# Snowflake.net
KiCad netlist of a schematic drawn in Altium Designer
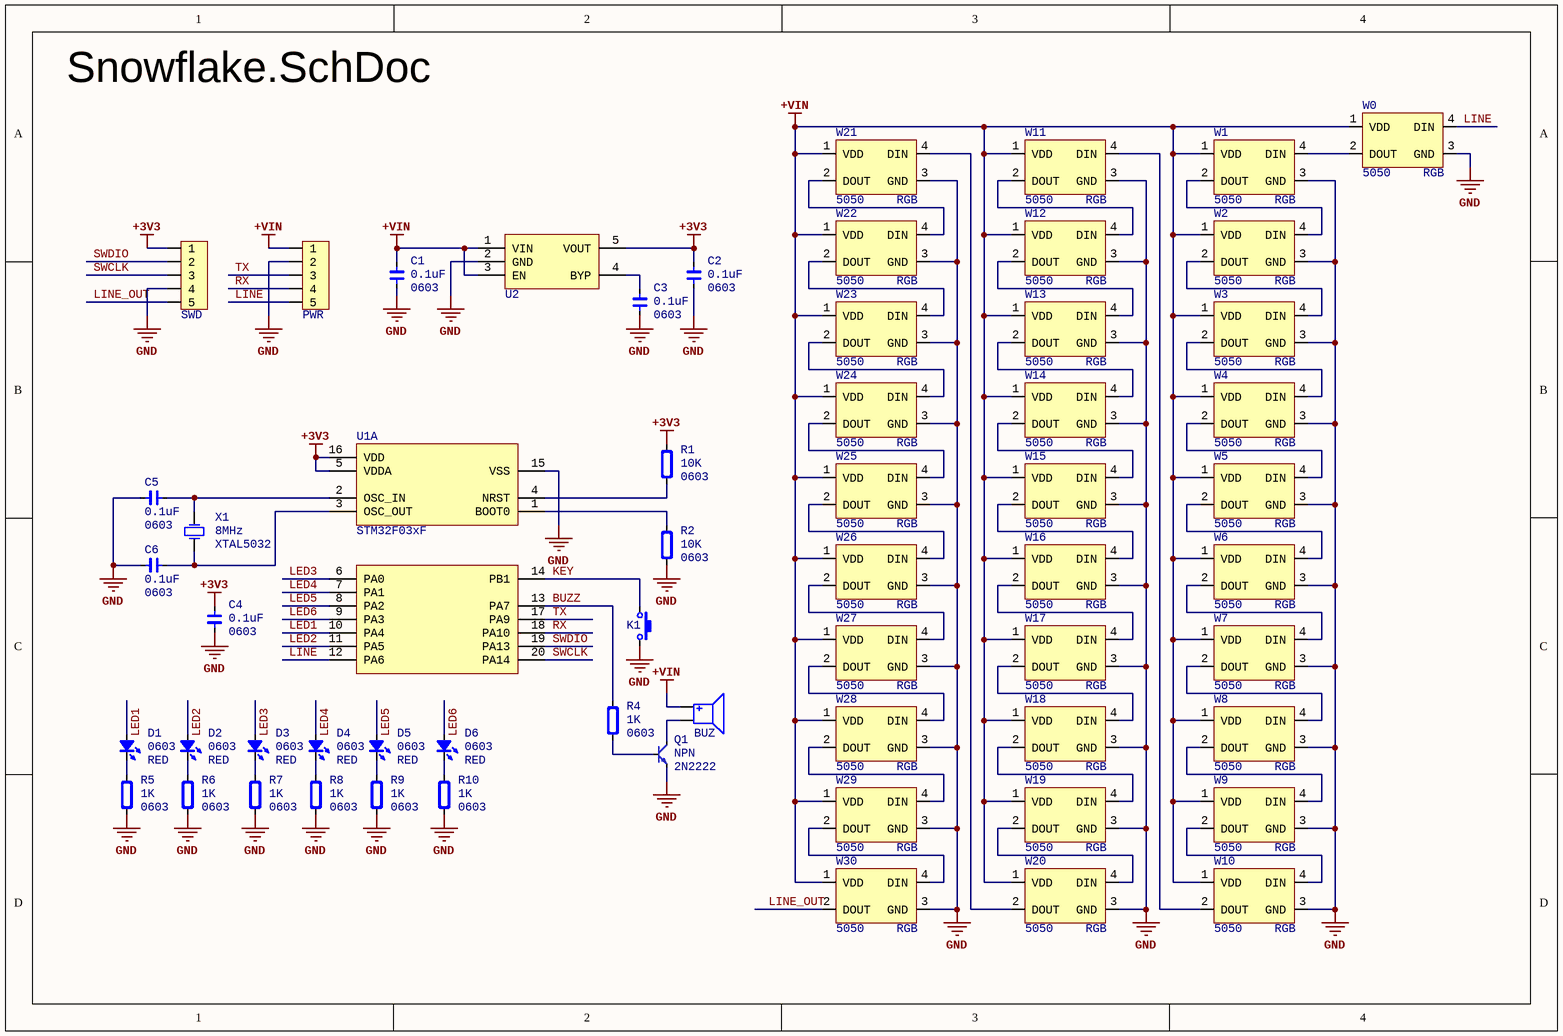
[diagram p0: Snowflake.SchDoc]

(export (version "E")
  (design (tool "Eeschema 10.0.6"))
  (components
    (comp (ref "BUZ")
      (value "Buzzer")
      (footprint "PCB_Module:Buzzer_5x5")
      (libsource (lib "SCH_Module") (part "Buzzer"))
    )
    (comp (ref "C1")
      (value "0.1uF")
      (footprint "PCB_PassiveCap:CAP_0603")
      (description "Capacitor")
      (fields (field (name "TYPE") "0603"))
      (libsource (lib "SCH_Passive") (part "Cap_0603"))
    )
    (comp (ref "C2")
      (value "0.1uF")
      (footprint "PCB_PassiveCap:CAP_0603")
      (description "Capacitor")
      (fields (field (name "TYPE") "0603"))
      (libsource (lib "SCH_Passive") (part "Cap_0603"))
    )
    (comp (ref "C3")
      (value "0.1uF")
      (footprint "PCB_PassiveCap:CAP_0603")
      (description "Capacitor")
      (fields (field (name "TYPE") "0603"))
      (libsource (lib "SCH_Passive") (part "Cap_0603"))
    )
    (comp (ref "C4")
      (value "0.1uF")
      (footprint "PCB_PassiveCap:CAP_0603")
      (description "Capacitor")
      (fields (field (name "TYPE") "0603"))
      (libsource (lib "SCH_Passive") (part "Cap_0603"))
    )
    (comp (ref "C5")
      (value "0.1uF")
      (footprint "PCB_PassiveCap:CAP_0603")
      (description "Capacitor")
      (fields (field (name "TYPE") "0603"))
      (libsource (lib "") (part "Cap_0603_1"))
    )
    (comp (ref "C6")
      (value "0.1uF")
      (footprint "PCB_PassiveCap:CAP_0603")
      (description "Capacitor")
      (fields (field (name "TYPE") "0603"))
      (libsource (lib "") (part "Cap_0603_1"))
    )
    (comp (ref "D1")
      (value "RED")
      (footprint "PCB_ActiveLED:LED_0603_RED")
      (description "LED")
      (fields (field (name "TYPE") "0603"))
      (libsource (lib "SCH_Active") (part "LED_0603"))
    )
    (comp (ref "D2")
      (value "RED")
      (footprint "PCB_ActiveLED:LED_0603_RED")
      (description "LED")
      (fields (field (name "TYPE") "0603"))
      (libsource (lib "SCH_Active") (part "LED_0603"))
    )
    (comp (ref "D3")
      (value "RED")
      (footprint "PCB_ActiveLED:LED_0603_RED")
      (description "LED")
      (fields (field (name "TYPE") "0603"))
      (libsource (lib "SCH_Active") (part "LED_0603"))
    )
    (comp (ref "D4")
      (value "RED")
      (footprint "PCB_ActiveLED:LED_0603_RED")
      (description "LED")
      (fields (field (name "TYPE") "0603"))
      (libsource (lib "SCH_Active") (part "LED_0603"))
    )
    (comp (ref "D5")
      (value "RED")
      (footprint "PCB_ActiveLED:LED_0603_RED")
      (description "LED")
      (fields (field (name "TYPE") "0603"))
      (libsource (lib "SCH_Active") (part "LED_0603"))
    )
    (comp (ref "D6")
      (value "RED")
      (footprint "PCB_ActiveLED:LED_0603_RED")
      (description "LED")
      (fields (field (name "TYPE") "0603"))
      (libsource (lib "SCH_Active") (part "LED_0603"))
    )
    (comp (ref "K1")
      (value "ButtonTACT")
      (footprint "PCB_Switch:ButtonTACT_3x4x2_180")
      (description "Button")
      (libsource (lib "SCH_Switch") (part "ButtonTACT_3x4x2_180"))
    )
    (comp (ref "PWR")
      (value "HDR1x5_2.54")
      (footprint "PCB_ConnectorHDR:HDR1X5_2.54_180")
      (description "Header")
      (libsource (lib "SCH_ConnectorHDR") (part "HDR1x5_2.54"))
    )
    (comp (ref "Q1")
      (value "NPN")
      (footprint "PCB_IntegratedCircuit:SOT23-3")
      (description "Transistor")
      (fields (field (name "TYPE") "2N2222"))
      (libsource (lib "SCH_Active") (part "BJT_NPN"))
    )
    (comp (ref "R1")
      (value "10K")
      (footprint "PCB_PassiveRes:RES_0603")
      (description "Resistor")
      (fields (field (name "TYPE") "0603"))
      (libsource (lib "SCH_Passive") (part "Res_0603"))
    )
    (comp (ref "R2")
      (value "10K")
      (footprint "PCB_PassiveRes:RES_0603")
      (description "Resistor")
      (fields (field (name "TYPE") "0603"))
      (libsource (lib "SCH_Passive") (part "Res_0603"))
    )
    (comp (ref "R4")
      (value "1K")
      (footprint "PCB_PassiveRes:RES_0603")
      (description "Resistor")
      (fields (field (name "TYPE") "0603"))
      (libsource (lib "SCH_Passive") (part "Res_0603"))
    )
    (comp (ref "R5")
      (value "1K")
      (footprint "PCB_PassiveRes:RES_0603")
      (description "Resistor")
      (fields (field (name "TYPE") "0603"))
      (libsource (lib "SCH_Passive") (part "Res_0603"))
    )
    (comp (ref "R6")
      (value "1K")
      (footprint "PCB_PassiveRes:RES_0603")
      (description "Resistor")
      (fields (field (name "TYPE") "0603"))
      (libsource (lib "SCH_Passive") (part "Res_0603"))
    )
    (comp (ref "R7")
      (value "1K")
      (footprint "PCB_PassiveRes:RES_0603")
      (description "Resistor")
      (fields (field (name "TYPE") "0603"))
      (libsource (lib "SCH_Passive") (part "Res_0603"))
    )
    (comp (ref "R8")
      (value "1K")
      (footprint "PCB_PassiveRes:RES_0603")
      (description "Resistor")
      (fields (field (name "TYPE") "0603"))
      (libsource (lib "SCH_Passive") (part "Res_0603"))
    )
    (comp (ref "R9")
      (value "1K")
      (footprint "PCB_PassiveRes:RES_0603")
      (description "Resistor")
      (fields (field (name "TYPE") "0603"))
      (libsource (lib "SCH_Passive") (part "Res_0603"))
    )
    (comp (ref "R10")
      (value "1K")
      (footprint "PCB_PassiveRes:RES_0603")
      (description "Resistor")
      (fields (field (name "TYPE") "0603"))
      (libsource (lib "SCH_Passive") (part "Res_0603"))
    )
    (comp (ref "SWD")
      (value "HDR1x5_2.54")
      (footprint "PCB_ConnectorHDR:HDR1X5_2.54_180")
      (description "Header")
      (libsource (lib "SCH_ConnectorHDR") (part "HDR1x5_2.54"))
    )
    (comp (ref "U1")
      (value "STM32F03xF")
      (footprint "PCB_IntegratedCircuit:TSSOP_E170_P0.65_20")
      (description "MCU")
      (libsource (lib "SCH_IntegratedCircuit") (part "STM32F03xF"))
    )
    (comp (ref "U2")
      (value "RT9193")
      (footprint "PCB_IntegratedCircuit:SOT23-5")
      (description "Power")
      (libsource (lib "SCH_IntegratedCircuit") (part "RT9193"))
    )
    (comp (ref "W0")
      (value "RGB")
      (footprint "PCB_ActiveLED:LED_5050_WS2812B")
      (description "LED")
      (fields (field (name "TYPE") "5050"))
      (libsource (lib "SCH_Active") (part "LED_5050_WS2812B"))
    )
    (comp (ref "W1")
      (value "RGB")
      (footprint "PCB_ActiveLED:LED_5050_WS2812B")
      (description "LED")
      (fields (field (name "TYPE") "5050"))
      (libsource (lib "SCH_Active") (part "LED_5050_WS2812B"))
    )
    (comp (ref "W2")
      (value "RGB")
      (footprint "PCB_ActiveLED:LED_5050_WS2812B")
      (description "LED")
      (fields (field (name "TYPE") "5050"))
      (libsource (lib "SCH_Active") (part "LED_5050_WS2812B"))
    )
    (comp (ref "W3")
      (value "RGB")
      (footprint "PCB_ActiveLED:LED_5050_WS2812B")
      (description "LED")
      (fields (field (name "TYPE") "5050"))
      (libsource (lib "SCH_Active") (part "LED_5050_WS2812B"))
    )
    (comp (ref "W4")
      (value "RGB")
      (footprint "PCB_ActiveLED:LED_5050_WS2812B")
      (description "LED")
      (fields (field (name "TYPE") "5050"))
      (libsource (lib "SCH_Active") (part "LED_5050_WS2812B"))
    )
    (comp (ref "W5")
      (value "RGB")
      (footprint "PCB_ActiveLED:LED_5050_WS2812B")
      (description "LED")
      (fields (field (name "TYPE") "5050"))
      (libsource (lib "SCH_Active") (part "LED_5050_WS2812B"))
    )
    (comp (ref "W6")
      (value "RGB")
      (footprint "PCB_ActiveLED:LED_5050_WS2812B")
      (description "LED")
      (fields (field (name "TYPE") "5050"))
      (libsource (lib "SCH_Active") (part "LED_5050_WS2812B"))
    )
    (comp (ref "W7")
      (value "RGB")
      (footprint "PCB_ActiveLED:LED_5050_WS2812B")
      (description "LED")
      (fields (field (name "TYPE") "5050"))
      (libsource (lib "SCH_Active") (part "LED_5050_WS2812B"))
    )
    (comp (ref "W8")
      (value "RGB")
      (footprint "PCB_ActiveLED:LED_5050_WS2812B")
      (description "LED")
      (fields (field (name "TYPE") "5050"))
      (libsource (lib "SCH_Active") (part "LED_5050_WS2812B"))
    )
    (comp (ref "W9")
      (value "RGB")
      (footprint "PCB_ActiveLED:LED_5050_WS2812B")
      (description "LED")
      (fields (field (name "TYPE") "5050"))
      (libsource (lib "SCH_Active") (part "LED_5050_WS2812B"))
    )
    (comp (ref "W10")
      (value "RGB")
      (footprint "PCB_ActiveLED:LED_5050_WS2812B")
      (description "LED")
      (fields (field (name "TYPE") "5050"))
      (libsource (lib "SCH_Active") (part "LED_5050_WS2812B"))
    )
    (comp (ref "W11")
      (value "RGB")
      (footprint "PCB_ActiveLED:LED_5050_WS2812B")
      (description "LED")
      (fields (field (name "TYPE") "5050"))
      (libsource (lib "SCH_Active") (part "LED_5050_WS2812B"))
    )
    (comp (ref "W12")
      (value "RGB")
      (footprint "PCB_ActiveLED:LED_5050_WS2812B")
      (description "LED")
      (fields (field (name "TYPE") "5050"))
      (libsource (lib "SCH_Active") (part "LED_5050_WS2812B"))
    )
    (comp (ref "W13")
      (value "RGB")
      (footprint "PCB_ActiveLED:LED_5050_WS2812B")
      (description "LED")
      (fields (field (name "TYPE") "5050"))
      (libsource (lib "SCH_Active") (part "LED_5050_WS2812B"))
    )
    (comp (ref "W14")
      (value "RGB")
      (footprint "PCB_ActiveLED:LED_5050_WS2812B")
      (description "LED")
      (fields (field (name "TYPE") "5050"))
      (libsource (lib "SCH_Active") (part "LED_5050_WS2812B"))
    )
    (comp (ref "W15")
      (value "RGB")
      (footprint "PCB_ActiveLED:LED_5050_WS2812B")
      (description "LED")
      (fields (field (name "TYPE") "5050"))
      (libsource (lib "SCH_Active") (part "LED_5050_WS2812B"))
    )
    (comp (ref "W16")
      (value "RGB")
      (footprint "PCB_ActiveLED:LED_5050_WS2812B")
      (description "LED")
      (fields (field (name "TYPE") "5050"))
      (libsource (lib "SCH_Active") (part "LED_5050_WS2812B"))
    )
    (comp (ref "W17")
      (value "RGB")
      (footprint "PCB_ActiveLED:LED_5050_WS2812B")
      (description "LED")
      (fields (field (name "TYPE") "5050"))
      (libsource (lib "SCH_Active") (part "LED_5050_WS2812B"))
    )
    (comp (ref "W18")
      (value "RGB")
      (footprint "PCB_ActiveLED:LED_5050_WS2812B")
      (description "LED")
      (fields (field (name "TYPE") "5050"))
      (libsource (lib "SCH_Active") (part "LED_5050_WS2812B"))
    )
    (comp (ref "W19")
      (value "RGB")
      (footprint "PCB_ActiveLED:LED_5050_WS2812B")
      (description "LED")
      (fields (field (name "TYPE") "5050"))
      (libsource (lib "SCH_Active") (part "LED_5050_WS2812B"))
    )
    (comp (ref "W20")
      (value "RGB")
      (footprint "PCB_ActiveLED:LED_5050_WS2812B")
      (description "LED")
      (fields (field (name "TYPE") "5050"))
      (libsource (lib "SCH_Active") (part "LED_5050_WS2812B"))
    )
    (comp (ref "W21")
      (value "RGB")
      (footprint "PCB_ActiveLED:LED_5050_WS2812B")
      (description "LED")
      (fields (field (name "TYPE") "5050"))
      (libsource (lib "SCH_Active") (part "LED_5050_WS2812B"))
    )
    (comp (ref "W22")
      (value "RGB")
      (footprint "PCB_ActiveLED:LED_5050_WS2812B")
      (description "LED")
      (fields (field (name "TYPE") "5050"))
      (libsource (lib "SCH_Active") (part "LED_5050_WS2812B"))
    )
    (comp (ref "W23")
      (value "RGB")
      (footprint "PCB_ActiveLED:LED_5050_WS2812B")
      (description "LED")
      (fields (field (name "TYPE") "5050"))
      (libsource (lib "SCH_Active") (part "LED_5050_WS2812B"))
    )
    (comp (ref "W24")
      (value "RGB")
      (footprint "PCB_ActiveLED:LED_5050_WS2812B")
      (description "LED")
      (fields (field (name "TYPE") "5050"))
      (libsource (lib "SCH_Active") (part "LED_5050_WS2812B"))
    )
    (comp (ref "W25")
      (value "RGB")
      (footprint "PCB_ActiveLED:LED_5050_WS2812B")
      (description "LED")
      (fields (field (name "TYPE") "5050"))
      (libsource (lib "SCH_Active") (part "LED_5050_WS2812B"))
    )
    (comp (ref "W26")
      (value "RGB")
      (footprint "PCB_ActiveLED:LED_5050_WS2812B")
      (description "LED")
      (fields (field (name "TYPE") "5050"))
      (libsource (lib "SCH_Active") (part "LED_5050_WS2812B"))
    )
    (comp (ref "W27")
      (value "RGB")
      (footprint "PCB_ActiveLED:LED_5050_WS2812B")
      (description "LED")
      (fields (field (name "TYPE") "5050"))
      (libsource (lib "SCH_Active") (part "LED_5050_WS2812B"))
    )
    (comp (ref "W28")
      (value "RGB")
      (footprint "PCB_ActiveLED:LED_5050_WS2812B")
      (description "LED")
      (fields (field (name "TYPE") "5050"))
      (libsource (lib "SCH_Active") (part "LED_5050_WS2812B"))
    )
    (comp (ref "W29")
      (value "RGB")
      (footprint "PCB_ActiveLED:LED_5050_WS2812B")
      (description "LED")
      (fields (field (name "TYPE") "5050"))
      (libsource (lib "SCH_Active") (part "LED_5050_WS2812B"))
    )
    (comp (ref "W30")
      (value "RGB")
      (footprint "PCB_ActiveLED:LED_5050_WS2812B")
      (description "LED")
      (fields (field (name "TYPE") "5050"))
      (libsource (lib "SCH_Active") (part "LED_5050_WS2812B"))
    )
    (comp (ref "X1")
      (value "8MHz")
      (footprint "PCB_Oscillator:XT_5032_2")
      (description "Crystal Oscillator")
      (fields (field (name "TYPE") "XTAL5032"))
      (libsource (lib "SCH_Oscillator") (part "XTAL_5032_2P"))
    )
  )
  (nets
    (net (code "1") (name "+3V3") (class "Default")
      (node (ref "C2") (pin "2") (pinfunction "2_2") (pintype "passive"))
      (node (ref "C4") (pin "2") (pinfunction "2_2") (pintype "passive"))
      (node (ref "R1") (pin "2") (pinfunction "2_2") (pintype "passive"))
      (node (ref "SWD") (pin "1") (pinfunction "1_1") (pintype "passive"))
      (node (ref "U1") (pin "16") (pinfunction "VDD_16") (pintype "passive"))
      (node (ref "U1") (pin "5") (pinfunction "VDDA_5") (pintype "passive"))
      (node (ref "U2") (pin "5") (pinfunction "VOUT_5") (pintype "passive"))
    )
    (net (code "2") (name "+VIN") (class "Default")
      (node (ref "BUZ") (pin "P") (pinfunction "Positive_P") (pintype "passive"))
      (node (ref "C1") (pin "2") (pinfunction "2_2") (pintype "passive"))
      (node (ref "PWR") (pin "1") (pinfunction "1_1") (pintype "passive"))
      (node (ref "U2") (pin "1") (pinfunction "VIN_1") (pintype "passive"))
      (node (ref "U2") (pin "3") (pinfunction "EN_3") (pintype "power_in"))
      (node (ref "W0") (pin "1") (pinfunction "VDD_1") (pintype "passive"))
      (node (ref "W1") (pin "1") (pinfunction "VDD_1") (pintype "passive"))
      (node (ref "W10") (pin "1") (pinfunction "VDD_1") (pintype "passive"))
      (node (ref "W11") (pin "1") (pinfunction "VDD_1") (pintype "passive"))
      (node (ref "W12") (pin "1") (pinfunction "VDD_1") (pintype "passive"))
      (node (ref "W13") (pin "1") (pinfunction "VDD_1") (pintype "passive"))
      (node (ref "W14") (pin "1") (pinfunction "VDD_1") (pintype "passive"))
      (node (ref "W15") (pin "1") (pinfunction "VDD_1") (pintype "passive"))
      (node (ref "W16") (pin "1") (pinfunction "VDD_1") (pintype "passive"))
      (node (ref "W17") (pin "1") (pinfunction "VDD_1") (pintype "passive"))
      (node (ref "W18") (pin "1") (pinfunction "VDD_1") (pintype "passive"))
      (node (ref "W19") (pin "1") (pinfunction "VDD_1") (pintype "passive"))
      (node (ref "W2") (pin "1") (pinfunction "VDD_1") (pintype "passive"))
      (node (ref "W20") (pin "1") (pinfunction "VDD_1") (pintype "passive"))
      (node (ref "W21") (pin "1") (pinfunction "VDD_1") (pintype "passive"))
      (node (ref "W22") (pin "1") (pinfunction "VDD_1") (pintype "passive"))
      (node (ref "W23") (pin "1") (pinfunction "VDD_1") (pintype "passive"))
      (node (ref "W24") (pin "1") (pinfunction "VDD_1") (pintype "passive"))
      (node (ref "W25") (pin "1") (pinfunction "VDD_1") (pintype "passive"))
      (node (ref "W26") (pin "1") (pinfunction "VDD_1") (pintype "passive"))
      (node (ref "W27") (pin "1") (pinfunction "VDD_1") (pintype "passive"))
      (node (ref "W28") (pin "1") (pinfunction "VDD_1") (pintype "passive"))
      (node (ref "W29") (pin "1") (pinfunction "VDD_1") (pintype "passive"))
      (node (ref "W3") (pin "1") (pinfunction "VDD_1") (pintype "passive"))
      (node (ref "W30") (pin "1") (pinfunction "VDD_1") (pintype "passive"))
      (node (ref "W4") (pin "1") (pinfunction "VDD_1") (pintype "passive"))
      (node (ref "W5") (pin "1") (pinfunction "VDD_1") (pintype "passive"))
      (node (ref "W6") (pin "1") (pinfunction "VDD_1") (pintype "passive"))
      (node (ref "W7") (pin "1") (pinfunction "VDD_1") (pintype "passive"))
      (node (ref "W8") (pin "1") (pinfunction "VDD_1") (pintype "passive"))
      (node (ref "W9") (pin "1") (pinfunction "VDD_1") (pintype "passive"))
    )
    (net (code "3") (name "/BUZZ") (class "Default")
      (node (ref "R4") (pin "1") (pinfunction "1_1") (pintype "passive"))
      (node (ref "U1") (pin "13") (pinfunction "PA7_13") (pintype "passive"))
    )
    (net (code "4") (name "/KEY") (class "Default")
      (node (ref "K1") (pin "1") (pinfunction "1_1") (pintype "passive"))
      (node (ref "U1") (pin "14") (pinfunction "PB1_14") (pintype "passive"))
    )
    (net (code "5") (name "/LED1") (class "Default")
      (node (ref "D1") (pin "1") (pinfunction "A_1") (pintype "passive"))
      (node (ref "U1") (pin "10") (pinfunction "PA4_10") (pintype "passive"))
    )
    (net (code "6") (name "/LED2") (class "Default")
      (node (ref "D2") (pin "1") (pinfunction "A_1") (pintype "passive"))
      (node (ref "U1") (pin "11") (pinfunction "PA5_11") (pintype "passive"))
    )
    (net (code "7") (name "/LED3") (class "Default")
      (node (ref "D3") (pin "1") (pinfunction "A_1") (pintype "passive"))
      (node (ref "U1") (pin "6") (pinfunction "PA0_6") (pintype "passive"))
    )
    (net (code "8") (name "/LED4") (class "Default")
      (node (ref "D4") (pin "1") (pinfunction "A_1") (pintype "passive"))
      (node (ref "U1") (pin "7") (pinfunction "PA1_7") (pintype "passive"))
    )
    (net (code "9") (name "/LED5") (class "Default")
      (node (ref "D5") (pin "1") (pinfunction "A_1") (pintype "passive"))
      (node (ref "U1") (pin "8") (pinfunction "PA2_8") (pintype "passive"))
    )
    (net (code "10") (name "/LED6") (class "Default")
      (node (ref "D6") (pin "1") (pinfunction "A_1") (pintype "passive"))
      (node (ref "U1") (pin "9") (pinfunction "PA3_9") (pintype "passive"))
    )
    (net (code "11") (name "/LINE") (class "Default")
      (node (ref "PWR") (pin "5") (pinfunction "5_5") (pintype "passive"))
      (node (ref "U1") (pin "12") (pinfunction "PA6_12") (pintype "passive"))
      (node (ref "W0") (pin "4") (pinfunction "DIN_4") (pintype "passive"))
    )
    (net (code "12") (name "/LINE_OUT") (class "Default")
      (node (ref "SWD") (pin "5") (pinfunction "5_5") (pintype "passive"))
      (node (ref "W30") (pin "2") (pinfunction "DOUT_2") (pintype "passive"))
    )
    (net (code "13") (name "/RX") (class "Default")
      (node (ref "PWR") (pin "4") (pinfunction "4_4") (pintype "passive"))
      (node (ref "U1") (pin "18") (pinfunction "PA10_18") (pintype "passive"))
    )
    (net (code "14") (name "/SWCLK") (class "Default")
      (node (ref "SWD") (pin "3") (pinfunction "3_3") (pintype "passive"))
      (node (ref "U1") (pin "20") (pinfunction "PA14_20") (pintype "passive"))
    )
    (net (code "15") (name "/SWDIO") (class "Default")
      (node (ref "SWD") (pin "2") (pinfunction "2_2") (pintype "passive"))
      (node (ref "U1") (pin "19") (pinfunction "PA13_19") (pintype "passive"))
    )
    (net (code "16") (name "/TX") (class "Default")
      (node (ref "PWR") (pin "3") (pinfunction "3_3") (pintype "passive"))
      (node (ref "U1") (pin "17") (pinfunction "PA9_17") (pintype "passive"))
    )
    (net (code "17") (name "GND") (class "Default")
      (node (ref "C1") (pin "1") (pinfunction "1_1") (pintype "passive"))
      (node (ref "C2") (pin "1") (pinfunction "1_1") (pintype "passive"))
      (node (ref "C3") (pin "1") (pinfunction "1_1") (pintype "passive"))
      (node (ref "C4") (pin "1") (pinfunction "1_1") (pintype "passive"))
      (node (ref "C5") (pin "1") (pinfunction "1_1") (pintype "passive"))
      (node (ref "C6") (pin "1") (pinfunction "1_1") (pintype "passive"))
      (node (ref "K1") (pin "2") (pinfunction "2_2") (pintype "passive"))
      (node (ref "PWR") (pin "2") (pinfunction "2_2") (pintype "passive"))
      (node (ref "Q1") (pin "2") (pinfunction "E_2") (pintype "passive"))
      (node (ref "R10") (pin "1") (pinfunction "1_1") (pintype "passive"))
      (node (ref "R2") (pin "1") (pinfunction "1_1") (pintype "passive"))
      (node (ref "R5") (pin "1") (pinfunction "1_1") (pintype "passive"))
      (node (ref "R6") (pin "1") (pinfunction "1_1") (pintype "passive"))
      (node (ref "R7") (pin "1") (pinfunction "1_1") (pintype "passive"))
      (node (ref "R8") (pin "1") (pinfunction "1_1") (pintype "passive"))
      (node (ref "R9") (pin "1") (pinfunction "1_1") (pintype "passive"))
      (node (ref "SWD") (pin "4") (pinfunction "4_4") (pintype "passive"))
      (node (ref "U1") (pin "15") (pinfunction "VSS_15") (pintype "passive"))
      (node (ref "U2") (pin "2") (pinfunction "GND_2") (pintype "passive"))
      (node (ref "W0") (pin "3") (pinfunction "GND_3") (pintype "passive"))
      (node (ref "W1") (pin "3") (pinfunction "GND_3") (pintype "passive"))
      (node (ref "W10") (pin "3") (pinfunction "GND_3") (pintype "passive"))
      (node (ref "W11") (pin "3") (pinfunction "GND_3") (pintype "passive"))
      (node (ref "W12") (pin "3") (pinfunction "GND_3") (pintype "passive"))
      (node (ref "W13") (pin "3") (pinfunction "GND_3") (pintype "passive"))
      (node (ref "W14") (pin "3") (pinfunction "GND_3") (pintype "passive"))
      (node (ref "W15") (pin "3") (pinfunction "GND_3") (pintype "passive"))
      (node (ref "W16") (pin "3") (pinfunction "GND_3") (pintype "passive"))
      (node (ref "W17") (pin "3") (pinfunction "GND_3") (pintype "passive"))
      (node (ref "W18") (pin "3") (pinfunction "GND_3") (pintype "passive"))
      (node (ref "W19") (pin "3") (pinfunction "GND_3") (pintype "passive"))
      (node (ref "W2") (pin "3") (pinfunction "GND_3") (pintype "passive"))
      (node (ref "W20") (pin "3") (pinfunction "GND_3") (pintype "passive"))
      (node (ref "W21") (pin "3") (pinfunction "GND_3") (pintype "passive"))
      (node (ref "W22") (pin "3") (pinfunction "GND_3") (pintype "passive"))
      (node (ref "W23") (pin "3") (pinfunction "GND_3") (pintype "passive"))
      (node (ref "W24") (pin "3") (pinfunction "GND_3") (pintype "passive"))
      (node (ref "W25") (pin "3") (pinfunction "GND_3") (pintype "passive"))
      (node (ref "W26") (pin "3") (pinfunction "GND_3") (pintype "passive"))
      (node (ref "W27") (pin "3") (pinfunction "GND_3") (pintype "passive"))
      (node (ref "W28") (pin "3") (pinfunction "GND_3") (pintype "passive"))
      (node (ref "W29") (pin "3") (pinfunction "GND_3") (pintype "passive"))
      (node (ref "W3") (pin "3") (pinfunction "GND_3") (pintype "passive"))
      (node (ref "W30") (pin "3") (pinfunction "GND_3") (pintype "passive"))
      (node (ref "W4") (pin "3") (pinfunction "GND_3") (pintype "passive"))
      (node (ref "W5") (pin "3") (pinfunction "GND_3") (pintype "passive"))
      (node (ref "W6") (pin "3") (pinfunction "GND_3") (pintype "passive"))
      (node (ref "W7") (pin "3") (pinfunction "GND_3") (pintype "passive"))
      (node (ref "W8") (pin "3") (pinfunction "GND_3") (pintype "passive"))
      (node (ref "W9") (pin "3") (pinfunction "GND_3") (pintype "passive"))
    )
    (net (code "18") (name "Net-(BUZ-Negative)") (class "Default")
      (node (ref "BUZ") (pin "N") (pinfunction "Negative_N") (pintype "passive"))
      (node (ref "Q1") (pin "3") (pinfunction "C_3") (pintype "passive"))
    )
    (net (code "19") (name "Net-(D1-K)") (class "Default")
      (node (ref "D1") (pin "2") (pinfunction "K_2") (pintype "passive"))
      (node (ref "R5") (pin "2") (pinfunction "2_2") (pintype "passive"))
    )
    (net (code "20") (name "Net-(D2-K)") (class "Default")
      (node (ref "D2") (pin "2") (pinfunction "K_2") (pintype "passive"))
      (node (ref "R6") (pin "2") (pinfunction "2_2") (pintype "passive"))
    )
    (net (code "21") (name "Net-(D3-K)") (class "Default")
      (node (ref "D3") (pin "2") (pinfunction "K_2") (pintype "passive"))
      (node (ref "R7") (pin "2") (pinfunction "2_2") (pintype "passive"))
    )
    (net (code "22") (name "Net-(D4-K)") (class "Default")
      (node (ref "D4") (pin "2") (pinfunction "K_2") (pintype "passive"))
      (node (ref "R8") (pin "2") (pinfunction "2_2") (pintype "passive"))
    )
    (net (code "23") (name "Net-(D5-K)") (class "Default")
      (node (ref "D5") (pin "2") (pinfunction "K_2") (pintype "passive"))
      (node (ref "R9") (pin "2") (pinfunction "2_2") (pintype "passive"))
    )
    (net (code "24") (name "Net-(D6-K)") (class "Default")
      (node (ref "D6") (pin "2") (pinfunction "K_2") (pintype "passive"))
      (node (ref "R10") (pin "2") (pinfunction "2_2") (pintype "passive"))
    )
    (net (code "25") (name "Net-(Q1-B)") (class "Default")
      (node (ref "Q1") (pin "1") (pinfunction "B_1") (pintype "passive"))
      (node (ref "R4") (pin "2") (pinfunction "2_2") (pintype "passive"))
    )
    (net (code "26") (name "Net-(U1A-BOOT0)") (class "Default")
      (node (ref "R2") (pin "2") (pinfunction "2_2") (pintype "passive"))
      (node (ref "U1") (pin "1") (pinfunction "BOOT0_1") (pintype "passive"))
    )
    (net (code "27") (name "Net-(U1A-NRST)") (class "Default")
      (node (ref "R1") (pin "1") (pinfunction "1_1") (pintype "passive"))
      (node (ref "U1") (pin "4") (pinfunction "NRST_4") (pintype "passive"))
    )
    (net (code "28") (name "Net-(U1A-OSC_IN)") (class "Default")
      (node (ref "C5") (pin "2") (pinfunction "2_2") (pintype "passive"))
      (node (ref "U1") (pin "2") (pinfunction "OSC_IN_2") (pintype "passive"))
      (node (ref "X1") (pin "2") (pinfunction "OSC2_2") (pintype "passive"))
    )
    (net (code "29") (name "Net-(U1A-OSC_OUT)") (class "Default")
      (node (ref "C6") (pin "2") (pinfunction "2_2") (pintype "passive"))
      (node (ref "U1") (pin "3") (pinfunction "OSC_OUT_3") (pintype "passive"))
      (node (ref "X1") (pin "1") (pinfunction "OSC1_1") (pintype "passive"))
    )
    (net (code "30") (name "Net-(U2-BYP)") (class "Default")
      (node (ref "C3") (pin "2") (pinfunction "2_2") (pintype "passive"))
      (node (ref "U2") (pin "4") (pinfunction "BYP_4") (pintype "passive"))
    )
    (net (code "31") (name "Net-(W0-DOUT)") (class "Default")
      (node (ref "W0") (pin "2") (pinfunction "DOUT_2") (pintype "passive"))
      (node (ref "W1") (pin "4") (pinfunction "DIN_4") (pintype "passive"))
    )
    (net (code "32") (name "Net-(W1-DOUT)") (class "Default")
      (node (ref "W1") (pin "2") (pinfunction "DOUT_2") (pintype "passive"))
      (node (ref "W2") (pin "4") (pinfunction "DIN_4") (pintype "passive"))
    )
    (net (code "33") (name "Net-(W2-DOUT)") (class "Default")
      (node (ref "W2") (pin "2") (pinfunction "DOUT_2") (pintype "passive"))
      (node (ref "W3") (pin "4") (pinfunction "DIN_4") (pintype "passive"))
    )
    (net (code "34") (name "Net-(W3-DOUT)") (class "Default")
      (node (ref "W3") (pin "2") (pinfunction "DOUT_2") (pintype "passive"))
      (node (ref "W4") (pin "4") (pinfunction "DIN_4") (pintype "passive"))
    )
    (net (code "35") (name "Net-(W4-DOUT)") (class "Default")
      (node (ref "W4") (pin "2") (pinfunction "DOUT_2") (pintype "passive"))
      (node (ref "W5") (pin "4") (pinfunction "DIN_4") (pintype "passive"))
    )
    (net (code "36") (name "Net-(W5-DOUT)") (class "Default")
      (node (ref "W5") (pin "2") (pinfunction "DOUT_2") (pintype "passive"))
      (node (ref "W6") (pin "4") (pinfunction "DIN_4") (pintype "passive"))
    )
    (net (code "37") (name "Net-(W6-DOUT)") (class "Default")
      (node (ref "W6") (pin "2") (pinfunction "DOUT_2") (pintype "passive"))
      (node (ref "W7") (pin "4") (pinfunction "DIN_4") (pintype "passive"))
    )
    (net (code "38") (name "Net-(W7-DOUT)") (class "Default")
      (node (ref "W7") (pin "2") (pinfunction "DOUT_2") (pintype "passive"))
      (node (ref "W8") (pin "4") (pinfunction "DIN_4") (pintype "passive"))
    )
    (net (code "39") (name "Net-(W8-DOUT)") (class "Default")
      (node (ref "W8") (pin "2") (pinfunction "DOUT_2") (pintype "passive"))
      (node (ref "W9") (pin "4") (pinfunction "DIN_4") (pintype "passive"))
    )
    (net (code "40") (name "Net-(W10-DIN)") (class "Default")
      (node (ref "W10") (pin "4") (pinfunction "DIN_4") (pintype "passive"))
      (node (ref "W9") (pin "2") (pinfunction "DOUT_2") (pintype "passive"))
    )
    (net (code "41") (name "Net-(W10-DOUT)") (class "Default")
      (node (ref "W10") (pin "2") (pinfunction "DOUT_2") (pintype "passive"))
      (node (ref "W11") (pin "4") (pinfunction "DIN_4") (pintype "passive"))
    )
    (net (code "42") (name "Net-(W11-DOUT)") (class "Default")
      (node (ref "W11") (pin "2") (pinfunction "DOUT_2") (pintype "passive"))
      (node (ref "W12") (pin "4") (pinfunction "DIN_4") (pintype "passive"))
    )
    (net (code "43") (name "Net-(W12-DOUT)") (class "Default")
      (node (ref "W12") (pin "2") (pinfunction "DOUT_2") (pintype "passive"))
      (node (ref "W13") (pin "4") (pinfunction "DIN_4") (pintype "passive"))
    )
    (net (code "44") (name "Net-(W13-DOUT)") (class "Default")
      (node (ref "W13") (pin "2") (pinfunction "DOUT_2") (pintype "passive"))
      (node (ref "W14") (pin "4") (pinfunction "DIN_4") (pintype "passive"))
    )
    (net (code "45") (name "Net-(W14-DOUT)") (class "Default")
      (node (ref "W14") (pin "2") (pinfunction "DOUT_2") (pintype "passive"))
      (node (ref "W15") (pin "4") (pinfunction "DIN_4") (pintype "passive"))
    )
    (net (code "46") (name "Net-(W15-DOUT)") (class "Default")
      (node (ref "W15") (pin "2") (pinfunction "DOUT_2") (pintype "passive"))
      (node (ref "W16") (pin "4") (pinfunction "DIN_4") (pintype "passive"))
    )
    (net (code "47") (name "Net-(W16-DOUT)") (class "Default")
      (node (ref "W16") (pin "2") (pinfunction "DOUT_2") (pintype "passive"))
      (node (ref "W17") (pin "4") (pinfunction "DIN_4") (pintype "passive"))
    )
    (net (code "48") (name "Net-(W17-DOUT)") (class "Default")
      (node (ref "W17") (pin "2") (pinfunction "DOUT_2") (pintype "passive"))
      (node (ref "W18") (pin "4") (pinfunction "DIN_4") (pintype "passive"))
    )
    (net (code "49") (name "Net-(W18-DOUT)") (class "Default")
      (node (ref "W18") (pin "2") (pinfunction "DOUT_2") (pintype "passive"))
      (node (ref "W19") (pin "4") (pinfunction "DIN_4") (pintype "passive"))
    )
    (net (code "50") (name "Net-(W19-DOUT)") (class "Default")
      (node (ref "W19") (pin "2") (pinfunction "DOUT_2") (pintype "passive"))
      (node (ref "W20") (pin "4") (pinfunction "DIN_4") (pintype "passive"))
    )
    (net (code "51") (name "Net-(W20-DOUT)") (class "Default")
      (node (ref "W20") (pin "2") (pinfunction "DOUT_2") (pintype "passive"))
      (node (ref "W21") (pin "4") (pinfunction "DIN_4") (pintype "passive"))
    )
    (net (code "52") (name "Net-(W21-DOUT)") (class "Default")
      (node (ref "W21") (pin "2") (pinfunction "DOUT_2") (pintype "passive"))
      (node (ref "W22") (pin "4") (pinfunction "DIN_4") (pintype "passive"))
    )
    (net (code "53") (name "Net-(W22-DOUT)") (class "Default")
      (node (ref "W22") (pin "2") (pinfunction "DOUT_2") (pintype "passive"))
      (node (ref "W23") (pin "4") (pinfunction "DIN_4") (pintype "passive"))
    )
    (net (code "54") (name "Net-(W23-DOUT)") (class "Default")
      (node (ref "W23") (pin "2") (pinfunction "DOUT_2") (pintype "passive"))
      (node (ref "W24") (pin "4") (pinfunction "DIN_4") (pintype "passive"))
    )
    (net (code "55") (name "Net-(W24-DOUT)") (class "Default")
      (node (ref "W24") (pin "2") (pinfunction "DOUT_2") (pintype "passive"))
      (node (ref "W25") (pin "4") (pinfunction "DIN_4") (pintype "passive"))
    )
    (net (code "56") (name "Net-(W25-DOUT)") (class "Default")
      (node (ref "W25") (pin "2") (pinfunction "DOUT_2") (pintype "passive"))
      (node (ref "W26") (pin "4") (pinfunction "DIN_4") (pintype "passive"))
    )
    (net (code "57") (name "Net-(W26-DOUT)") (class "Default")
      (node (ref "W26") (pin "2") (pinfunction "DOUT_2") (pintype "passive"))
      (node (ref "W27") (pin "4") (pinfunction "DIN_4") (pintype "passive"))
    )
    (net (code "58") (name "Net-(W27-DOUT)") (class "Default")
      (node (ref "W27") (pin "2") (pinfunction "DOUT_2") (pintype "passive"))
      (node (ref "W28") (pin "4") (pinfunction "DIN_4") (pintype "passive"))
    )
    (net (code "59") (name "Net-(W28-DOUT)") (class "Default")
      (node (ref "W28") (pin "2") (pinfunction "DOUT_2") (pintype "passive"))
      (node (ref "W29") (pin "4") (pinfunction "DIN_4") (pintype "passive"))
    )
    (net (code "60") (name "Net-(W29-DOUT)") (class "Default")
      (node (ref "W29") (pin "2") (pinfunction "DOUT_2") (pintype "passive"))
      (node (ref "W30") (pin "4") (pinfunction "DIN_4") (pintype "passive"))
    )
  )
)
